# 7-segment.net
KiCad netlist of a schematic drawn in Altium Designer
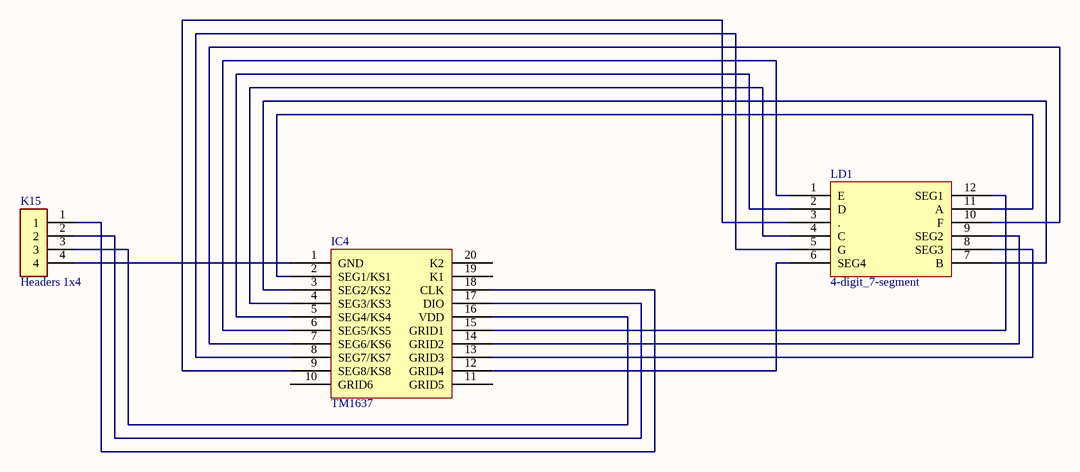
[diagram p0: 7-segment.SchDoc]

(export (version "E")
  (design (tool "Eeschema 10.0.6"))
  (components
    (comp (ref "IC4")
      (value "TM1637")
      (footprint "TM1637")
      (description "Led Drive Control Special Circuit")
      (libsource (lib "project-2022") (part "TM1637"))
    )
    (comp (ref "K15")
      (value "Headers 1x4")
      (footprint "Headers 1x4")
      (description "Connector")
      (fields (field (name "MANUFACTURER_PART_NUMBER") "2-826646-0"))
      (libsource (lib "project-2022") (part "Headers 1x4"))
    )
    (comp (ref "LD1")
      (value "4-digit_7-segment")
      (footprint "4-digit_7-segment")
      (libsource (lib "project-2022") (part "4-digit_7-segment"))
    )
  )
  (nets
    (net (code "1") (name "Net-(IC4-CLK)") (class "Default")
      (node (ref "IC4") (pin "18") (pinfunction "CLK_18") (pintype "passive"))
      (node (ref "K15") (pin "1") (pinfunction "1_1") (pintype "passive"))
    )
    (net (code "2") (name "Net-(IC4-DIO)") (class "Default")
      (node (ref "IC4") (pin "17") (pinfunction "DIO_17") (pintype "passive"))
      (node (ref "K15") (pin "2") (pinfunction "2_2") (pintype "passive"))
    )
    (net (code "3") (name "Net-(IC4-GND)") (class "Default")
      (node (ref "IC4") (pin "1") (pinfunction "GND_1") (pintype "passive"))
      (node (ref "K15") (pin "4") (pinfunction "4_4") (pintype "passive"))
    )
    (net (code "4") (name "Net-(IC4-GRID1)") (class "Default")
      (node (ref "IC4") (pin "15") (pinfunction "GRID1_15") (pintype "passive"))
      (node (ref "LD1") (pin "12") (pinfunction "SEG1_12") (pintype "passive"))
    )
    (net (code "5") (name "Net-(IC4-GRID2)") (class "Default")
      (node (ref "IC4") (pin "14") (pinfunction "GRID2_14") (pintype "passive"))
      (node (ref "LD1") (pin "9") (pinfunction "SEG2_9") (pintype "passive"))
    )
    (net (code "6") (name "Net-(IC4-GRID3)") (class "Default")
      (node (ref "IC4") (pin "13") (pinfunction "GRID3_13") (pintype "passive"))
      (node (ref "LD1") (pin "8") (pinfunction "SEG3_8") (pintype "passive"))
    )
    (net (code "7") (name "Net-(IC4-GRID4)") (class "Default")
      (node (ref "IC4") (pin "12") (pinfunction "GRID4_12") (pintype "passive"))
      (node (ref "LD1") (pin "6") (pinfunction "SEG4_6") (pintype "passive"))
    )
    (net (code "8") (name "Net-(IC4-SEG1{slash}KS1)") (class "Default")
      (node (ref "IC4") (pin "2") (pinfunction "SEG1/KS1_2") (pintype "passive"))
      (node (ref "LD1") (pin "11") (pinfunction "A_11") (pintype "passive"))
    )
    (net (code "9") (name "Net-(IC4-SEG2{slash}KS2)") (class "Default")
      (node (ref "IC4") (pin "3") (pinfunction "SEG2/KS2_3") (pintype "passive"))
      (node (ref "LD1") (pin "7") (pinfunction "B_7") (pintype "passive"))
    )
    (net (code "10") (name "Net-(IC4-SEG3{slash}KS3)") (class "Default")
      (node (ref "IC4") (pin "4") (pinfunction "SEG3/KS3_4") (pintype "passive"))
      (node (ref "LD1") (pin "4") (pinfunction "C_4") (pintype "passive"))
    )
    (net (code "11") (name "Net-(IC4-SEG4{slash}KS4)") (class "Default")
      (node (ref "IC4") (pin "5") (pinfunction "SEG4/KS4_5") (pintype "passive"))
      (node (ref "LD1") (pin "2") (pinfunction "D_2") (pintype "passive"))
    )
    (net (code "12") (name "Net-(IC4-SEG5{slash}KS5)") (class "Default")
      (node (ref "IC4") (pin "6") (pinfunction "SEG5/KS5_6") (pintype "passive"))
      (node (ref "LD1") (pin "1") (pinfunction "E_1") (pintype "passive"))
    )
    (net (code "13") (name "Net-(IC4-SEG6{slash}KS6)") (class "Default")
      (node (ref "IC4") (pin "7") (pinfunction "SEG6/KS6_7") (pintype "passive"))
      (node (ref "LD1") (pin "10") (pinfunction "F_10") (pintype "passive"))
    )
    (net (code "14") (name "Net-(IC4-SEG7{slash}KS7)") (class "Default")
      (node (ref "IC4") (pin "8") (pinfunction "SEG7/KS7_8") (pintype "passive"))
      (node (ref "LD1") (pin "5") (pinfunction "G_5") (pintype "passive"))
    )
    (net (code "15") (name "Net-(IC4-SEG8{slash}KS8)") (class "Default")
      (node (ref "IC4") (pin "9") (pinfunction "SEG8/KS8_9") (pintype "passive"))
      (node (ref "LD1") (pin "3") (pinfunction "._3") (pintype "passive"))
    )
    (net (code "16") (name "Net-(IC4-VDD)") (class "Default")
      (node (ref "IC4") (pin "16") (pinfunction "VDD_16") (pintype "passive"))
      (node (ref "K15") (pin "3") (pinfunction "3_3") (pintype "passive"))
    )
    (net (code "17") (name "unconnected-(IC4-GRID5-Pad11)") (class "Default")
      (node (ref "IC4") (pin "11") (pinfunction "GRID5_11") (pintype "passive"))
    )
    (net (code "18") (name "unconnected-(IC4-GRID6-Pad10)") (class "Default")
      (node (ref "IC4") (pin "10") (pinfunction "GRID6_10") (pintype "passive"))
    )
    (net (code "19") (name "unconnected-(IC4-K1-Pad19)") (class "Default")
      (node (ref "IC4") (pin "19") (pinfunction "K1_19") (pintype "passive"))
    )
    (net (code "20") (name "unconnected-(IC4-K2-Pad20)") (class "Default")
      (node (ref "IC4") (pin "20") (pinfunction "K2_20") (pintype "passive"))
    )
  )
)
